# MCU_RTC_DIAGRAM_REV1_0.net
KiCad netlist of a schematic drawn in EAGLE
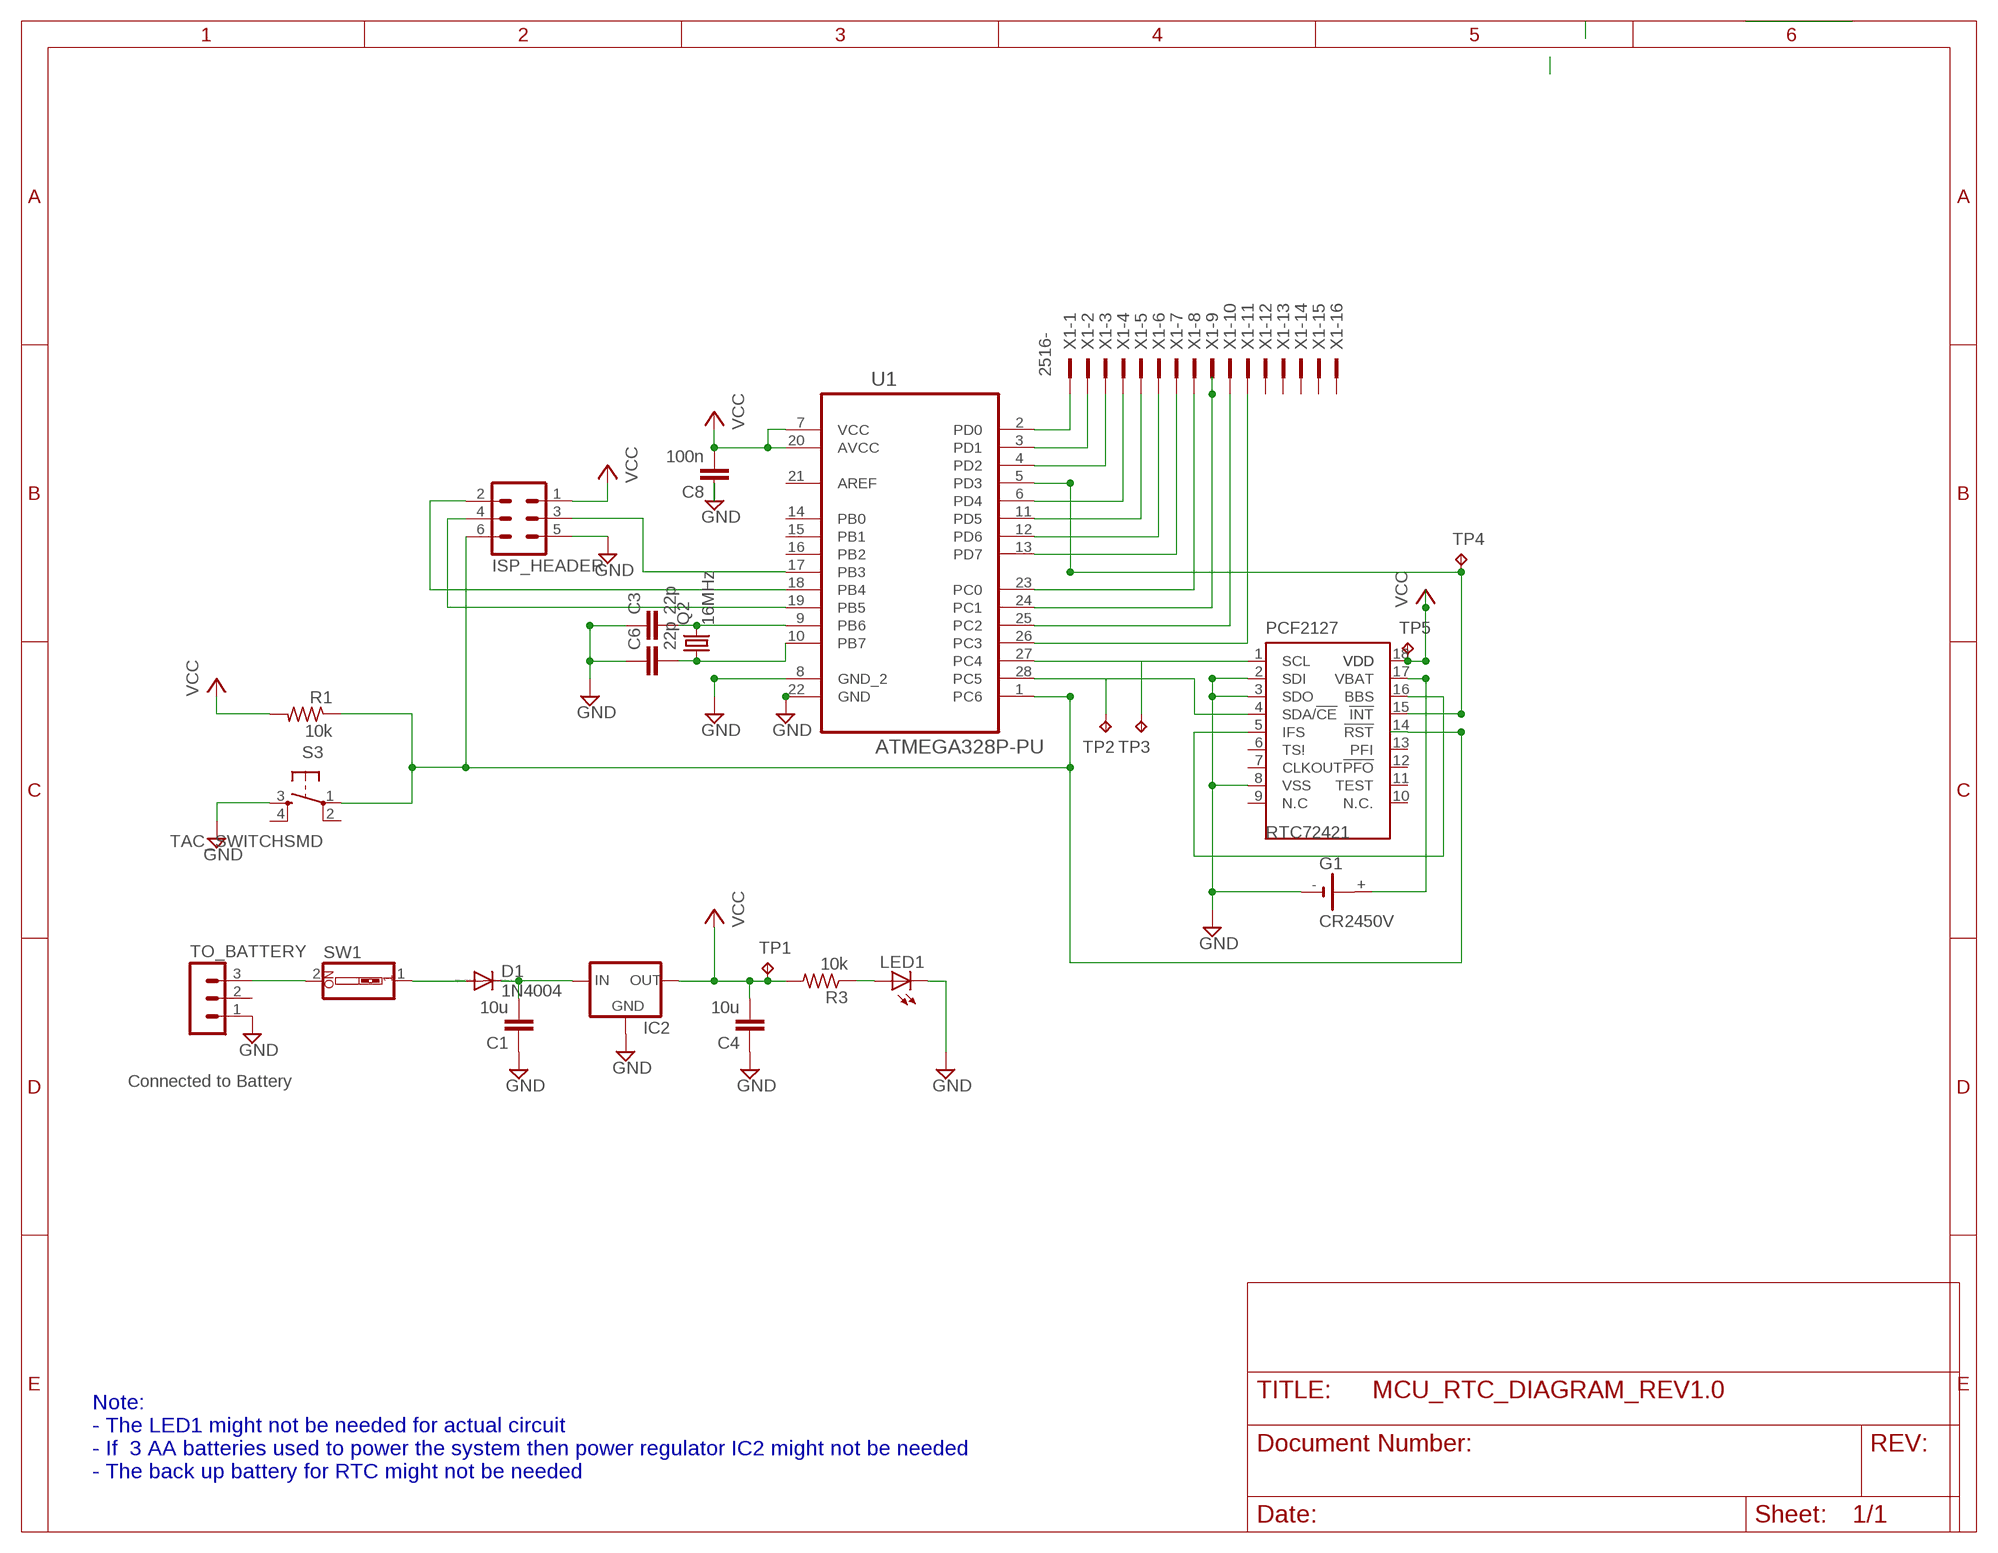
[diagram p0: schematic, sheet 1]

(export (version "E")
  (design (tool "Eeschema 10.0.6"))
  (components
    (comp (ref "C1")
      (value "10u")
      (footprint "eagle-import:C0805")
      (libsource (lib "eagle-import") (part "C-EUC0805"))
    )
    (comp (ref "C3")
      (value "22p")
      (footprint "eagle-import:C0805")
      (libsource (lib "eagle-import") (part "C-EUC0805"))
    )
    (comp (ref "C4")
      (value "10u")
      (footprint "eagle-import:C0805")
      (libsource (lib "eagle-import") (part "C-EUC0805"))
    )
    (comp (ref "C6")
      (value "22p")
      (footprint "eagle-import:C0805")
      (libsource (lib "eagle-import") (part "C-EUC0805"))
    )
    (comp (ref "C8")
      (value "100n")
      (footprint "eagle-import:C0805")
      (libsource (lib "eagle-import") (part "C-EUC0805"))
    )
    (comp (ref "D1")
      (value "1N4004")
      (footprint "eagle-import:DO41-10")
      (libsource (lib "eagle-import") (part "1N4004"))
    )
    (comp (ref "G1")
      (value "CR2450V")
      (footprint "eagle-import:CR2450V")
      (libsource (lib "eagle-import") (part "CR2450V"))
    )
    (comp (ref "IC1")
      (value "RTC72421")
      (footprint "eagle-import:DIL18")
      (fields (field (name "MPN") "RTC72421B"))
      (libsource (lib "eagle-import") (part "RTC72421"))
    )
    (comp (ref "IC2")
      (value "78XXL")
      (footprint "eagle-import:78XXL")
      (libsource (lib "eagle-import") (part "78XXL"))
    )
    (comp (ref "ISP_HEADER")
      (value "MA03-2")
      (footprint "eagle-import:MA03-2")
      (libsource (lib "eagle-import") (part "MA03-2"))
    )
    (comp (ref "LED1")
      (value "LEDCHIPLED_0805")
      (footprint "eagle-import:CHIPLED_0805")
      (libsource (lib "eagle-import") (part "LEDCHIPLED_0805"))
    )
    (comp (ref "Q2")
      (value "16MHz")
      (footprint "eagle-import:HC49_S")
      (libsource (lib "eagle-import") (part "CRYSTALHC49S"))
    )
    (comp (ref "R1")
      (value "10k")
      (footprint "eagle-import:R0805")
      (libsource (lib "eagle-import") (part "R-US_R0805"))
    )
    (comp (ref "R3")
      (value "10k")
      (footprint "eagle-import:R0805")
      (libsource (lib "eagle-import") (part "R-US_R0805"))
    )
    (comp (ref "S3")
      (value "TAC_SWITCHSMD")
      (footprint "eagle-import:TACTILE-SWITCH-SMD")
      (libsource (lib "eagle-import") (part "TAC_SWITCHSMD"))
    )
    (comp (ref "SW1")
      (value "SW_DIP-1")
      (footprint "eagle-import:EDG-01")
      (libsource (lib "eagle-import") (part "SW_DIP-1"))
    )
    (comp (ref "TO_BATTERY")
      (value "MA03-1")
      (footprint "eagle-import:MA03-1")
      (libsource (lib "eagle-import") (part "MA03-1"))
    )
    (comp (ref "TP1")
      (value "TPB1,27")
      (footprint "eagle-import:B1,27")
      (libsource (lib "eagle-import") (part "TPB1,27"))
    )
    (comp (ref "TP2")
      (value "TPB1,27")
      (footprint "eagle-import:B1,27")
      (libsource (lib "eagle-import") (part "TPB1,27"))
    )
    (comp (ref "TP3")
      (value "TPB1,27")
      (footprint "eagle-import:B1,27")
      (libsource (lib "eagle-import") (part "TPB1,27"))
    )
    (comp (ref "TP4")
      (value "TPB1,27")
      (footprint "eagle-import:B1,27")
      (libsource (lib "eagle-import") (part "TPB1,27"))
    )
    (comp (ref "TP5")
      (value "TPB1,27")
      (footprint "eagle-import:B1,27")
      (libsource (lib "eagle-import") (part "TPB1,27"))
    )
    (comp (ref "U1")
      (value "ATMEGA328P-PU")
      (footprint "eagle-import:DIP254P762X457-28")
      (libsource (lib "eagle-import") (part "ATMEGA328P-PU"))
    )
    (comp (ref "X1")
      (value "2516-")
      (footprint "eagle-import:PAK100_2500-16")
      (libsource (lib "eagle-import") (part "2516-"))
    )
  )
  (nets
    (net (code "1") (name "GND") (class "Default")
      (node (ref "C1") (pin "1") (pinfunction "1_1") (pintype "passive"))
      (node (ref "C3") (pin "1") (pinfunction "1_1") (pintype "passive"))
      (node (ref "C4") (pin "1") (pinfunction "1_1") (pintype "passive"))
      (node (ref "C6") (pin "1") (pinfunction "1_1") (pintype "passive"))
      (node (ref "C8") (pin "1") (pinfunction "1_1") (pintype "passive"))
      (node (ref "G1") (pin "-") (pinfunction "-_-") (pintype "passive"))
      (node (ref "IC1") (pin "2") (pinfunction "SDI_2") (pintype "input"))
      (node (ref "IC1") (pin "3") (pinfunction "SDO_3") (pintype "input"))
      (node (ref "IC1") (pin "8") (pinfunction "VSS_8") (pintype "input"))
      (node (ref "IC2") (pin "GND") (pinfunction "GND_GND") (pintype "input"))
      (node (ref "ISP_HEADER") (pin "5") (pinfunction "5_5") (pintype "passive"))
      (node (ref "LED1") (pin "C") (pinfunction "C_C") (pintype "passive"))
      (node (ref "S3") (pin "3") (pinfunction "3_3") (pintype "passive"))
      (node (ref "TO_BATTERY") (pin "1") (pinfunction "1_1") (pintype "passive"))
      (node (ref "U1") (pin "22") (pinfunction "GND_22") (pintype "passive"))
      (node (ref "U1") (pin "8") (pinfunction "GND_2_8") (pintype "passive"))
    )
    (net (code "2") (name "Net-(C1-Pad2)") (class "Default")
      (node (ref "C1") (pin "2") (pinfunction "2_2") (pintype "passive"))
      (node (ref "D1") (pin "C") (pinfunction "C_C") (pintype "passive"))
      (node (ref "IC2") (pin "IN") (pinfunction "IN_IN") (pintype "input"))
    )
    (net (code "3") (name "Net-(D1-PadA)") (class "Default")
      (node (ref "D1") (pin "A") (pinfunction "A_A") (pintype "passive"))
      (node (ref "SW1") (pin "1") (pinfunction "1_1") (pintype "passive"))
    )
    (net (code "4") (name "Net-(IC1-IFS)") (class "Default")
      (node (ref "IC1") (pin "16") (pinfunction "VCC_16") (pintype "power_in"))
      (node (ref "IC1") (pin "5") (pinfunction "IFS_5") (pintype "input"))
    )
    (net (code "5") (name "Net-(IC1-SCL)") (class "Default")
      (node (ref "IC1") (pin "1") (pinfunction "SCL_1") (pintype "input"))
      (node (ref "TP3") (pin "TP") (pinfunction "TP_TP") (pintype "input"))
      (node (ref "U1") (pin "27") (pinfunction "PC4_27") (pintype "bidirectional"))
    )
    (net (code "6") (name "Net-(IC1-SDA{slash}~{CE})") (class "Default")
      (node (ref "IC1") (pin "4") (pinfunction "SDA/~{CE}_4") (pintype "input"))
      (node (ref "TP2") (pin "TP") (pinfunction "TP_TP") (pintype "input"))
      (node (ref "U1") (pin "28") (pinfunction "PC5_28") (pintype "bidirectional"))
    )
    (net (code "7") (name "Net-(IC1-VBAT)") (class "Default")
      (node (ref "G1") (pin "+") (pinfunction "+_+") (pintype "passive"))
      (node (ref "IC1") (pin "17") (pinfunction "VBAT_17") (pintype "power_in"))
    )
    (net (code "8") (name "Net-(IC1-~{INT})") (class "Default")
      (node (ref "IC1") (pin "15") (pinfunction "~{INT}_15") (pintype "input"))
      (node (ref "TP4") (pin "TP") (pinfunction "TP_TP") (pintype "input"))
      (node (ref "U1") (pin "5") (pinfunction "PD3_5") (pintype "bidirectional"))
    )
    (net (code "9") (name "Net-(IC1-~{RST})") (class "Default")
      (node (ref "IC1") (pin "14") (pinfunction "~{RST}_14") (pintype "bidirectional"))
      (node (ref "ISP_HEADER") (pin "6") (pinfunction "6_6") (pintype "passive"))
      (node (ref "R1") (pin "1") (pinfunction "1_1") (pintype "passive"))
      (node (ref "S3") (pin "1") (pinfunction "1_1") (pintype "passive"))
      (node (ref "U1") (pin "1") (pinfunction "PC6_1") (pintype "bidirectional"))
    )
    (net (code "10") (name "Net-(LED1-PadA)") (class "Default")
      (node (ref "LED1") (pin "A") (pinfunction "A_A") (pintype "passive"))
      (node (ref "R3") (pin "1") (pinfunction "1_1") (pintype "passive"))
    )
    (net (code "11") (name "Net-(SW1-Pad2)") (class "Default")
      (node (ref "SW1") (pin "2") (pinfunction "2_2") (pintype "passive"))
      (node (ref "TO_BATTERY") (pin "3") (pinfunction "3_3") (pintype "passive"))
    )
    (net (code "12") (name "Net-(U1-PB3)") (class "Default")
      (node (ref "ISP_HEADER") (pin "3") (pinfunction "3_3") (pintype "passive"))
      (node (ref "U1") (pin "17") (pinfunction "PB3_17") (pintype "bidirectional"))
    )
    (net (code "13") (name "Net-(U1-PB4)") (class "Default")
      (node (ref "ISP_HEADER") (pin "2") (pinfunction "2_2") (pintype "passive"))
      (node (ref "U1") (pin "18") (pinfunction "PB4_18") (pintype "bidirectional"))
    )
    (net (code "14") (name "Net-(U1-PB5)") (class "Default")
      (node (ref "ISP_HEADER") (pin "4") (pinfunction "4_4") (pintype "passive"))
      (node (ref "U1") (pin "19") (pinfunction "PB5_19") (pintype "bidirectional"))
    )
    (net (code "15") (name "Net-(U1-PB6)") (class "Default")
      (node (ref "C3") (pin "2") (pinfunction "2_2") (pintype "passive"))
      (node (ref "Q2") (pin "2") (pinfunction "2_2") (pintype "passive"))
      (node (ref "U1") (pin "9") (pinfunction "PB6_9") (pintype "bidirectional"))
    )
    (net (code "16") (name "Net-(U1-PB7)") (class "Default")
      (node (ref "C6") (pin "2") (pinfunction "2_2") (pintype "passive"))
      (node (ref "Q2") (pin "1") (pinfunction "1_1") (pintype "passive"))
      (node (ref "U1") (pin "10") (pinfunction "PB7_10") (pintype "bidirectional"))
    )
    (net (code "17") (name "Net-(U1-PC0)") (class "Default")
      (node (ref "U1") (pin "23") (pinfunction "PC0_23") (pintype "bidirectional"))
      (node (ref "X1") (pin "8") (pinfunction "KL_8") (pintype "passive"))
    )
    (net (code "18") (name "Net-(U1-PC1)") (class "Default")
      (node (ref "U1") (pin "24") (pinfunction "PC1_24") (pintype "bidirectional"))
      (node (ref "X1") (pin "9") (pinfunction "KL_9") (pintype "passive"))
    )
    (net (code "19") (name "Net-(U1-PC2)") (class "Default")
      (node (ref "U1") (pin "25") (pinfunction "PC2_25") (pintype "bidirectional"))
      (node (ref "X1") (pin "10") (pinfunction "KL_10") (pintype "passive"))
    )
    (net (code "20") (name "Net-(U1-PC3)") (class "Default")
      (node (ref "U1") (pin "26") (pinfunction "PC3_26") (pintype "bidirectional"))
      (node (ref "X1") (pin "11") (pinfunction "KL_11") (pintype "passive"))
    )
    (net (code "21") (name "Net-(U1-PD0)") (class "Default")
      (node (ref "U1") (pin "2") (pinfunction "PD0_2") (pintype "bidirectional"))
      (node (ref "X1") (pin "1") (pinfunction "KL_1") (pintype "passive"))
    )
    (net (code "22") (name "Net-(U1-PD1)") (class "Default")
      (node (ref "U1") (pin "3") (pinfunction "PD1_3") (pintype "bidirectional"))
      (node (ref "X1") (pin "2") (pinfunction "KL_2") (pintype "passive"))
    )
    (net (code "23") (name "Net-(U1-PD2)") (class "Default")
      (node (ref "U1") (pin "4") (pinfunction "PD2_4") (pintype "bidirectional"))
      (node (ref "X1") (pin "3") (pinfunction "KL_3") (pintype "passive"))
    )
    (net (code "24") (name "Net-(U1-PD4)") (class "Default")
      (node (ref "U1") (pin "6") (pinfunction "PD4_6") (pintype "bidirectional"))
      (node (ref "X1") (pin "4") (pinfunction "KL_4") (pintype "passive"))
    )
    (net (code "25") (name "Net-(U1-PD5)") (class "Default")
      (node (ref "U1") (pin "11") (pinfunction "PD5_11") (pintype "bidirectional"))
      (node (ref "X1") (pin "5") (pinfunction "KL_5") (pintype "passive"))
    )
    (net (code "26") (name "Net-(U1-PD6)") (class "Default")
      (node (ref "U1") (pin "12") (pinfunction "PD6_12") (pintype "bidirectional"))
      (node (ref "X1") (pin "6") (pinfunction "KL_6") (pintype "passive"))
    )
    (net (code "27") (name "Net-(U1-PD7)") (class "Default")
      (node (ref "U1") (pin "13") (pinfunction "PD7_13") (pintype "bidirectional"))
      (node (ref "X1") (pin "7") (pinfunction "KL_7") (pintype "passive"))
    )
    (net (code "28") (name "VCC") (class "Default")
      (node (ref "C4") (pin "2") (pinfunction "2_2") (pintype "passive"))
      (node (ref "C8") (pin "2") (pinfunction "2_2") (pintype "passive"))
      (node (ref "IC1") (pin "18") (pinfunction "VDD_18") (pintype "power_in"))
      (node (ref "IC2") (pin "OUT") (pinfunction "OUT_OUT") (pintype "passive"))
      (node (ref "ISP_HEADER") (pin "1") (pinfunction "1_1") (pintype "passive"))
      (node (ref "R1") (pin "2") (pinfunction "2_2") (pintype "passive"))
      (node (ref "R3") (pin "2") (pinfunction "2_2") (pintype "passive"))
      (node (ref "TP1") (pin "TP") (pinfunction "TP_TP") (pintype "input"))
      (node (ref "TP5") (pin "TP") (pinfunction "TP_TP") (pintype "input"))
      (node (ref "U1") (pin "20") (pinfunction "AVCC_20") (pintype "power_in"))
      (node (ref "U1") (pin "7") (pinfunction "VCC_7") (pintype "power_in"))
    )
    (net (code "29") (name "unconnected-(G1-+-Pad+@1)") (class "Default")
      (node (ref "G1") (pin "+@1") (pinfunction "+_+@1") (pintype "passive"))
    )
    (net (code "30") (name "unconnected-(IC1-CLKOUT-Pad7)") (class "Default")
      (node (ref "IC1") (pin "7") (pinfunction "CLKOUT_7") (pintype "input"))
    )
    (net (code "31") (name "unconnected-(IC1-N.C-Pad9)") (class "Default")
      (node (ref "IC1") (pin "9") (pinfunction "N.C_9") (pintype "input"))
    )
    (net (code "32") (name "unconnected-(IC1-N.C.-Pad10)") (class "Default")
      (node (ref "IC1") (pin "10") (pinfunction "N.C._10") (pintype "input"))
    )
    (net (code "33") (name "unconnected-(IC1-PFI-Pad13)") (class "Default")
      (node (ref "IC1") (pin "13") (pinfunction "PFI_13") (pintype "bidirectional"))
    )
    (net (code "34") (name "unconnected-(IC1-TEST-Pad11)") (class "Default")
      (node (ref "IC1") (pin "11") (pinfunction "TEST_11") (pintype "bidirectional"))
    )
    (net (code "35") (name "unconnected-(IC1-TS~{}-Pad6)") (class "Default")
      (node (ref "IC1") (pin "6") (pinfunction "TS~{}_6") (pintype "input"))
    )
    (net (code "36") (name "unconnected-(IC1-~{PFO}-Pad12)") (class "Default")
      (node (ref "IC1") (pin "12") (pinfunction "~{PFO}_12") (pintype "bidirectional"))
    )
    (net (code "37") (name "unconnected-(S3-Pad2)") (class "Default")
      (node (ref "S3") (pin "2") (pinfunction "2_2") (pintype "passive"))
    )
    (net (code "38") (name "unconnected-(S3-Pad4)") (class "Default")
      (node (ref "S3") (pin "4") (pinfunction "4_4") (pintype "passive"))
    )
    (net (code "39") (name "unconnected-(TO_BATTERY-Pad2)") (class "Default")
      (node (ref "TO_BATTERY") (pin "2") (pinfunction "2_2") (pintype "passive"))
    )
    (net (code "40") (name "unconnected-(U1-AREF-Pad21)") (class "Default")
      (node (ref "U1") (pin "21") (pinfunction "AREF_21") (pintype "input"))
    )
    (net (code "41") (name "unconnected-(U1-PB0-Pad14)") (class "Default")
      (node (ref "U1") (pin "14") (pinfunction "PB0_14") (pintype "bidirectional"))
    )
    (net (code "42") (name "unconnected-(U1-PB1-Pad15)") (class "Default")
      (node (ref "U1") (pin "15") (pinfunction "PB1_15") (pintype "bidirectional"))
    )
    (net (code "43") (name "unconnected-(U1-PB2-Pad16)") (class "Default")
      (node (ref "U1") (pin "16") (pinfunction "PB2_16") (pintype "bidirectional"))
    )
    (net (code "44") (name "unconnected-(X1D-KL-Pad12)") (class "Default")
      (node (ref "X1") (pin "12") (pinfunction "KL_12") (pintype "passive"))
    )
    (net (code "45") (name "unconnected-(X1E-KL-Pad13)") (class "Default")
      (node (ref "X1") (pin "13") (pinfunction "KL_13") (pintype "passive"))
    )
    (net (code "46") (name "unconnected-(X1F-KL-Pad14)") (class "Default")
      (node (ref "X1") (pin "14") (pinfunction "KL_14") (pintype "passive"))
    )
    (net (code "47") (name "unconnected-(X1G-KL-Pad15)") (class "Default")
      (node (ref "X1") (pin "15") (pinfunction "KL_15") (pintype "passive"))
    )
    (net (code "48") (name "unconnected-(X1H-KL-Pad16)") (class "Default")
      (node (ref "X1") (pin "16") (pinfunction "KL_16") (pintype "passive"))
    )
  )
)
